# schematic.net
KiCad netlist of a schematic drawn in EAGLE
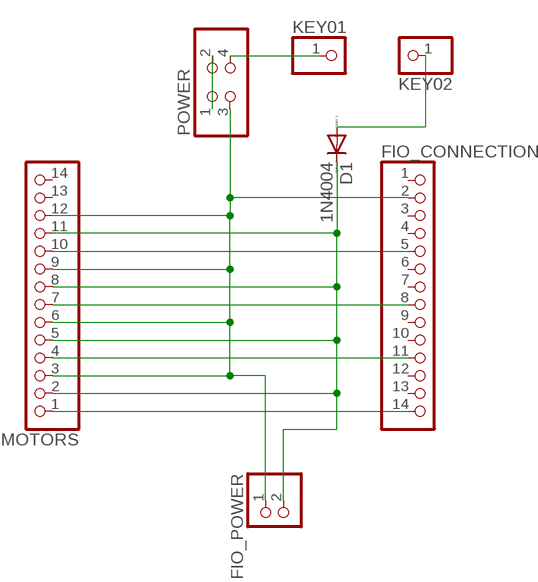
[diagram p0: schematic, sheet 1]

(export (version "E")
  (design (tool "Eeschema 10.0.6"))
  (components
    (comp (ref "D1")
      (value "1N4004")
      (footprint "eagle-import:DO41-10")
      (libsource (lib "eagle-import") (part "1N4004"))
    )
    (comp (ref "FIO_CONNECTION")
      (value "PINHD-1X14")
      (footprint "eagle-import:1X14")
      (libsource (lib "eagle-import") (part "PINHD-1X14"))
    )
    (comp (ref "FIO_POWER")
      (value "PINHD-1X2")
      (footprint "eagle-import:1X02")
      (libsource (lib "eagle-import") (part "PINHD-1X2"))
    )
    (comp (ref "KEY01")
      (value "PINHD-1X1")
      (footprint "eagle-import:1X01")
      (libsource (lib "eagle-import") (part "PINHD-1X1"))
    )
    (comp (ref "KEY02")
      (value "PINHD-1X1")
      (footprint "eagle-import:1X01")
      (libsource (lib "eagle-import") (part "PINHD-1X1"))
    )
    (comp (ref "MOTORS")
      (value "PINHD-1X14")
      (footprint "eagle-import:1X14")
      (libsource (lib "eagle-import") (part "PINHD-1X14"))
    )
    (comp (ref "POWER")
      (value "PINHD-2X2")
      (footprint "eagle-import:2X02")
      (libsource (lib "eagle-import") (part "PINHD-2X2"))
    )
  )
  (nets
    (net (code "1") (name "Net-(D1-PadA)") (class "Default")
      (node (ref "D1") (pin "A") (pinfunction "A_A") (pintype "passive"))
      (node (ref "KEY02") (pin "1") (pinfunction "1_1") (pintype "passive"))
    )
    (net (code "2") (name "Net-(D1-PadC)") (class "Default")
      (node (ref "D1") (pin "C") (pinfunction "C_C") (pintype "passive"))
      (node (ref "FIO_POWER") (pin "2") (pinfunction "2_2") (pintype "passive"))
      (node (ref "MOTORS") (pin "11") (pinfunction "11_11") (pintype "passive"))
      (node (ref "MOTORS") (pin "2") (pinfunction "2_2") (pintype "passive"))
      (node (ref "MOTORS") (pin "5") (pinfunction "5_5") (pintype "passive"))
      (node (ref "MOTORS") (pin "8") (pinfunction "8_8") (pintype "passive"))
    )
    (net (code "3") (name "Net-(FIO_CONNECTION-Pad2)") (class "Default")
      (node (ref "FIO_CONNECTION") (pin "2") (pinfunction "2_2") (pintype "passive"))
      (node (ref "FIO_POWER") (pin "1") (pinfunction "1_1") (pintype "passive"))
      (node (ref "MOTORS") (pin "12") (pinfunction "12_12") (pintype "passive"))
      (node (ref "MOTORS") (pin "3") (pinfunction "3_3") (pintype "passive"))
      (node (ref "MOTORS") (pin "6") (pinfunction "6_6") (pintype "passive"))
      (node (ref "MOTORS") (pin "9") (pinfunction "9_9") (pintype "passive"))
      (node (ref "POWER") (pin "3") (pinfunction "3_3") (pintype "passive"))
    )
    (net (code "4") (name "Net-(FIO_CONNECTION-Pad5)") (class "Default")
      (node (ref "FIO_CONNECTION") (pin "5") (pinfunction "5_5") (pintype "passive"))
      (node (ref "MOTORS") (pin "10") (pinfunction "10_10") (pintype "passive"))
    )
    (net (code "5") (name "Net-(FIO_CONNECTION-Pad8)") (class "Default")
      (node (ref "FIO_CONNECTION") (pin "8") (pinfunction "8_8") (pintype "passive"))
      (node (ref "MOTORS") (pin "7") (pinfunction "7_7") (pintype "passive"))
    )
    (net (code "6") (name "Net-(FIO_CONNECTION-Pad11)") (class "Default")
      (node (ref "FIO_CONNECTION") (pin "11") (pinfunction "11_11") (pintype "passive"))
      (node (ref "MOTORS") (pin "4") (pinfunction "4_4") (pintype "passive"))
    )
    (net (code "7") (name "Net-(FIO_CONNECTION-Pad14)") (class "Default")
      (node (ref "FIO_CONNECTION") (pin "14") (pinfunction "14_14") (pintype "passive"))
      (node (ref "MOTORS") (pin "1") (pinfunction "1_1") (pintype "passive"))
    )
    (net (code "8") (name "Net-(KEY01-Pad1)") (class "Default")
      (node (ref "KEY01") (pin "1") (pinfunction "1_1") (pintype "passive"))
      (node (ref "POWER") (pin "4") (pinfunction "4_4") (pintype "passive"))
    )
    (net (code "9") (name "Net-(POWER-Pad1)") (class "Default")
      (node (ref "POWER") (pin "1") (pinfunction "1_1") (pintype "passive"))
      (node (ref "POWER") (pin "2") (pinfunction "2_2") (pintype "passive"))
    )
    (net (code "10") (name "unconnected-(FIO_CONNECTION-Pad1)") (class "Default")
      (node (ref "FIO_CONNECTION") (pin "1") (pinfunction "1_1") (pintype "passive"))
    )
    (net (code "11") (name "unconnected-(FIO_CONNECTION-Pad3)") (class "Default")
      (node (ref "FIO_CONNECTION") (pin "3") (pinfunction "3_3") (pintype "passive"))
    )
    (net (code "12") (name "unconnected-(FIO_CONNECTION-Pad4)") (class "Default")
      (node (ref "FIO_CONNECTION") (pin "4") (pinfunction "4_4") (pintype "passive"))
    )
    (net (code "13") (name "unconnected-(FIO_CONNECTION-Pad6)") (class "Default")
      (node (ref "FIO_CONNECTION") (pin "6") (pinfunction "6_6") (pintype "passive"))
    )
    (net (code "14") (name "unconnected-(FIO_CONNECTION-Pad7)") (class "Default")
      (node (ref "FIO_CONNECTION") (pin "7") (pinfunction "7_7") (pintype "passive"))
    )
    (net (code "15") (name "unconnected-(FIO_CONNECTION-Pad9)") (class "Default")
      (node (ref "FIO_CONNECTION") (pin "9") (pinfunction "9_9") (pintype "passive"))
    )
    (net (code "16") (name "unconnected-(FIO_CONNECTION-Pad10)") (class "Default")
      (node (ref "FIO_CONNECTION") (pin "10") (pinfunction "10_10") (pintype "passive"))
    )
    (net (code "17") (name "unconnected-(FIO_CONNECTION-Pad12)") (class "Default")
      (node (ref "FIO_CONNECTION") (pin "12") (pinfunction "12_12") (pintype "passive"))
    )
    (net (code "18") (name "unconnected-(FIO_CONNECTION-Pad13)") (class "Default")
      (node (ref "FIO_CONNECTION") (pin "13") (pinfunction "13_13") (pintype "passive"))
    )
    (net (code "19") (name "unconnected-(MOTORS-Pad13)") (class "Default")
      (node (ref "MOTORS") (pin "13") (pinfunction "13_13") (pintype "passive"))
    )
    (net (code "20") (name "unconnected-(MOTORS-Pad14)") (class "Default")
      (node (ref "MOTORS") (pin "14") (pinfunction "14_14") (pintype "passive"))
    )
  )
)
